# MainBoard_ver2_2.net
KiCad netlist of a schematic drawn in EAGLE
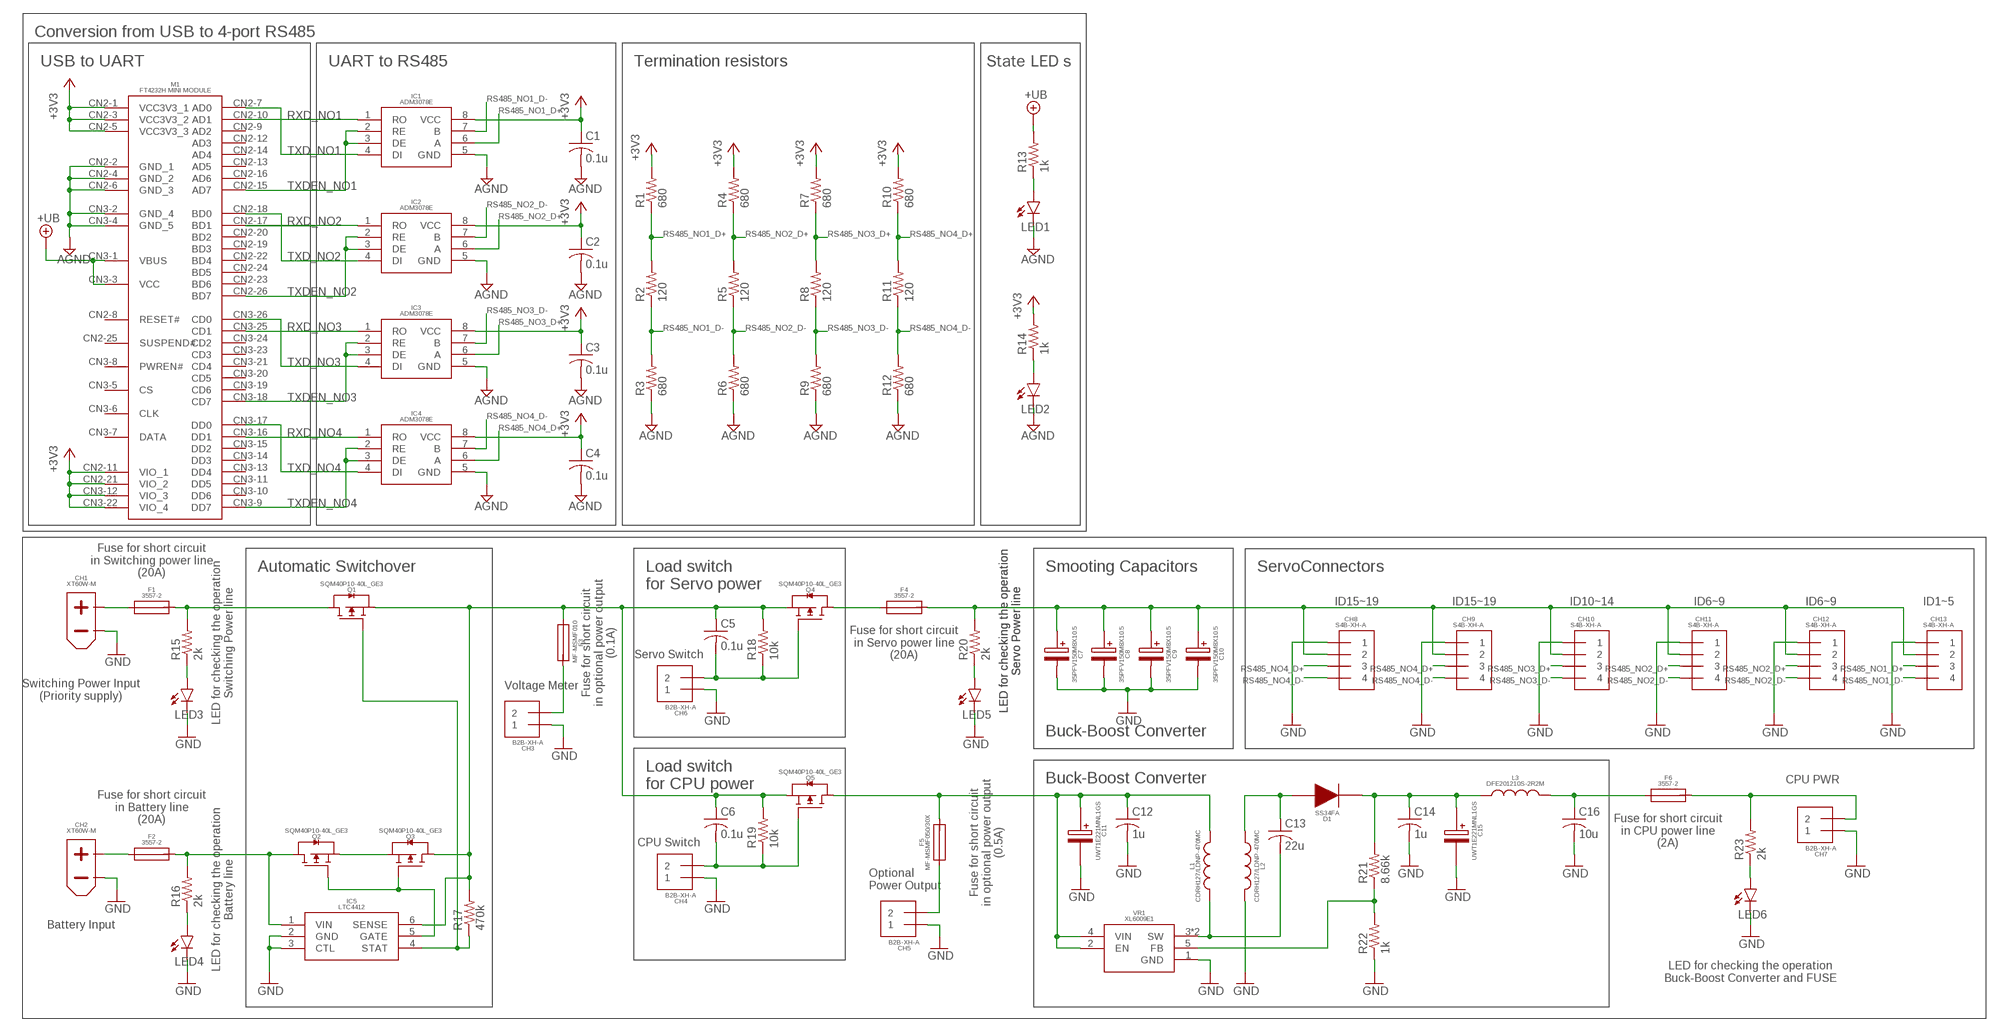
[diagram p0: schematic, sheet 1]

(export (version "E")
  (design (tool "Eeschema 10.0.6"))
  (components
    (comp (ref "C1")
      (value "0.1u")
      (footprint "eagle-import:C0603")
      (libsource (lib "eagle-import") (part "C-USC0603"))
    )
    (comp (ref "C2")
      (value "0.1u")
      (footprint "eagle-import:C0603")
      (libsource (lib "eagle-import") (part "C-USC0603"))
    )
    (comp (ref "C3")
      (value "0.1u")
      (footprint "eagle-import:C0603")
      (libsource (lib "eagle-import") (part "C-USC0603"))
    )
    (comp (ref "C4")
      (value "0.1u")
      (footprint "eagle-import:C0603")
      (libsource (lib "eagle-import") (part "C-USC0603"))
    )
    (comp (ref "C5")
      (value "0.1u")
      (footprint "eagle-import:C0603")
      (libsource (lib "eagle-import") (part "C-USC0603"))
    )
    (comp (ref "C6")
      (value "0.1u")
      (footprint "eagle-import:C0603")
      (libsource (lib "eagle-import") (part "C-USC0603"))
    )
    (comp (ref "C7")
      (value "35PFV150M8X10.5")
      (footprint "eagle-import:35PFV150M8X10.5")
      (libsource (lib "eagle-import") (part "35PFV150M8X10.5"))
    )
    (comp (ref "C8")
      (value "35PFV150M8X10.5")
      (footprint "eagle-import:35PFV150M8X10.5")
      (libsource (lib "eagle-import") (part "35PFV150M8X10.5"))
    )
    (comp (ref "C9")
      (value "35PFV150M8X10.5")
      (footprint "eagle-import:35PFV150M8X10.5")
      (libsource (lib "eagle-import") (part "35PFV150M8X10.5"))
    )
    (comp (ref "C10")
      (value "35PFV150M8X10.5")
      (footprint "eagle-import:35PFV150M8X10.5")
      (libsource (lib "eagle-import") (part "35PFV150M8X10.5"))
    )
    (comp (ref "C11")
      (value "UWT1E221MNL1GS")
      (footprint "eagle-import:UWT1E221MNL1GS")
      (libsource (lib "eagle-import") (part "UWT1E221MNL1GS"))
    )
    (comp (ref "C12")
      (value "1u")
      (footprint "eagle-import:C0603")
      (libsource (lib "eagle-import") (part "C-USC0603"))
    )
    (comp (ref "C13")
      (value "22u")
      (footprint "eagle-import:C2012")
      (libsource (lib "eagle-import") (part "C-USC2012"))
    )
    (comp (ref "C14")
      (value "1u")
      (footprint "eagle-import:C0603")
      (libsource (lib "eagle-import") (part "C-USC0603"))
    )
    (comp (ref "C15")
      (value "UWT1E221MNL1GS")
      (footprint "eagle-import:UWT1E221MNL1GS")
      (libsource (lib "eagle-import") (part "UWT1E221MNL1GS"))
    )
    (comp (ref "C16")
      (value "10u")
      (footprint "eagle-import:C0603")
      (libsource (lib "eagle-import") (part "C-USC0603"))
    )
    (comp (ref "CH1")
      (value "XT60PW-M")
      (footprint "eagle-import:XT60PW-M")
      (libsource (lib "eagle-import") (part "XT60PW-M"))
    )
    (comp (ref "CH2")
      (value "XT60PW-M")
      (footprint "eagle-import:XT60PW-M")
      (libsource (lib "eagle-import") (part "XT60PW-M"))
    )
    (comp (ref "CH3")
      (value "B2B-XH-A")
      (footprint "eagle-import:B2B-XH-A")
      (libsource (lib "eagle-import") (part "B2B-XH-A"))
    )
    (comp (ref "CH4")
      (value "B2B-XH-A")
      (footprint "eagle-import:B2B-XH-A")
      (libsource (lib "eagle-import") (part "B2B-XH-A"))
    )
    (comp (ref "CH5")
      (value "B2B-XH-A")
      (footprint "eagle-import:B2B-XH-A")
      (libsource (lib "eagle-import") (part "B2B-XH-A"))
    )
    (comp (ref "CH6")
      (value "B2B-XH-A")
      (footprint "eagle-import:B2B-XH-A")
      (libsource (lib "eagle-import") (part "B2B-XH-A"))
    )
    (comp (ref "CH7")
      (value "B2B-XH-A")
      (footprint "eagle-import:B2B-XH-A")
      (libsource (lib "eagle-import") (part "B2B-XH-A"))
    )
    (comp (ref "CH8")
      (value "S4B-XH-A")
      (footprint "eagle-import:S4B-XH-A")
      (libsource (lib "eagle-import") (part "S4B-XH-A"))
    )
    (comp (ref "CH9")
      (value "S4B-XH-A")
      (footprint "eagle-import:S4B-XH-A")
      (libsource (lib "eagle-import") (part "S4B-XH-A"))
    )
    (comp (ref "CH10")
      (value "S4B-XH-A")
      (footprint "eagle-import:S4B-XH-A")
      (libsource (lib "eagle-import") (part "S4B-XH-A"))
    )
    (comp (ref "CH11")
      (value "S4B-XH-A")
      (footprint "eagle-import:S4B-XH-A")
      (libsource (lib "eagle-import") (part "S4B-XH-A"))
    )
    (comp (ref "CH12")
      (value "S4B-XH-A")
      (footprint "eagle-import:S4B-XH-A")
      (libsource (lib "eagle-import") (part "S4B-XH-A"))
    )
    (comp (ref "CH13")
      (value "S4B-XH-A")
      (footprint "eagle-import:S4B-XH-A")
      (libsource (lib "eagle-import") (part "S4B-XH-A"))
    )
    (comp (ref "D1")
      (value "SS34FA")
      (footprint "eagle-import:SS34FA")
      (libsource (lib "eagle-import") (part "SS34FA"))
    )
    (comp (ref "F1")
      (value "3557-2")
      (footprint "eagle-import:3557-2")
      (libsource (lib "eagle-import") (part "3557-2"))
    )
    (comp (ref "F2")
      (value "3557-2")
      (footprint "eagle-import:3557-2")
      (libsource (lib "eagle-import") (part "3557-2"))
    )
    (comp (ref "F3")
      (value "MF-MSMF010")
      (footprint "eagle-import:MF-MSMF010")
      (libsource (lib "eagle-import") (part "MF-MSMF010"))
    )
    (comp (ref "F4")
      (value "3557-2")
      (footprint "eagle-import:3557-2")
      (libsource (lib "eagle-import") (part "3557-2"))
    )
    (comp (ref "F5")
      (value "MF-MSMF050/30X")
      (footprint "eagle-import:MF-MSMF050")
      (libsource (lib "eagle-import") (part "MF-MSMF050/30X"))
    )
    (comp (ref "F6")
      (value "3557-2")
      (footprint "eagle-import:3557-2")
      (libsource (lib "eagle-import") (part "3557-2"))
    )
    (comp (ref "IC1")
      (value "ADM3078E")
      (footprint "eagle-import:ADM3078E")
      (libsource (lib "eagle-import") (part "ADM3078E"))
    )
    (comp (ref "IC2")
      (value "ADM3078E")
      (footprint "eagle-import:ADM3078E")
      (libsource (lib "eagle-import") (part "ADM3078E"))
    )
    (comp (ref "IC3")
      (value "ADM3078E")
      (footprint "eagle-import:ADM3078E")
      (libsource (lib "eagle-import") (part "ADM3078E"))
    )
    (comp (ref "IC4")
      (value "ADM3078E")
      (footprint "eagle-import:ADM3078E")
      (libsource (lib "eagle-import") (part "ADM3078E"))
    )
    (comp (ref "IC5")
      (value "LTC4412")
      (footprint "eagle-import:LTC4412")
      (libsource (lib "eagle-import") (part "LTC4412"))
    )
    (comp (ref "L1")
      (value "CDRH127/LDNP-470MC")
      (footprint "eagle-import:CDRH127_LDNP")
      (libsource (lib "eagle-import") (part "CDRH127/LDNP-470MC"))
    )
    (comp (ref "L2")
      (value "CDRH127/LDNP-470MC")
      (footprint "eagle-import:CDRH127_LDNP")
      (libsource (lib "eagle-import") (part "CDRH127/LDNP-470MC"))
    )
    (comp (ref "L3")
      (value "DFE201210S-2R2M")
      (footprint "eagle-import:DFE201210S")
      (libsource (lib "eagle-import") (part "DFE201210S-2R2M"))
    )
    (comp (ref "LED1")
      (value "LEDSML0603")
      (footprint "eagle-import:SML0603")
      (libsource (lib "eagle-import") (part "LEDSML0603"))
    )
    (comp (ref "LED2")
      (value "LEDSML0603")
      (footprint "eagle-import:SML0603")
      (libsource (lib "eagle-import") (part "LEDSML0603"))
    )
    (comp (ref "LED3")
      (value "LEDSML0603")
      (footprint "eagle-import:SML0603")
      (libsource (lib "eagle-import") (part "LEDSML0603"))
    )
    (comp (ref "LED4")
      (value "LEDSML0603")
      (footprint "eagle-import:SML0603")
      (libsource (lib "eagle-import") (part "LEDSML0603"))
    )
    (comp (ref "LED5")
      (value "LEDSML0603")
      (footprint "eagle-import:SML0603")
      (libsource (lib "eagle-import") (part "LEDSML0603"))
    )
    (comp (ref "LED6")
      (value "LEDSML0603")
      (footprint "eagle-import:SML0603")
      (libsource (lib "eagle-import") (part "LEDSML0603"))
    )
    (comp (ref "M1")
      (value "FT4232H_MINI_MODULE")
      (footprint "eagle-import:FT4232H_MINI_MODULE")
      (libsource (lib "eagle-import") (part "FT4232H_MINI_MODULE"))
    )
    (comp (ref "Q1")
      (value "SQM40P10-40L_GE3")
      (footprint "eagle-import:TO-252-3")
      (libsource (lib "eagle-import") (part "SQM40P10-40L_GE3"))
    )
    (comp (ref "Q2")
      (value "SQM40P10-40L_GE3")
      (footprint "eagle-import:TO-252-3")
      (libsource (lib "eagle-import") (part "SQM40P10-40L_GE3"))
    )
    (comp (ref "Q3")
      (value "SQM40P10-40L_GE3")
      (footprint "eagle-import:TO-252-3")
      (libsource (lib "eagle-import") (part "SQM40P10-40L_GE3"))
    )
    (comp (ref "Q4")
      (value "SQM40P10-40L_GE3")
      (footprint "eagle-import:TO-252-3")
      (libsource (lib "eagle-import") (part "SQM40P10-40L_GE3"))
    )
    (comp (ref "Q5")
      (value "SQM40P10-40L_GE3")
      (footprint "eagle-import:TO-252-3")
      (libsource (lib "eagle-import") (part "SQM40P10-40L_GE3"))
    )
    (comp (ref "R1")
      (value "680")
      (footprint "eagle-import:R0603")
      (libsource (lib "eagle-import") (part "R-US_R0603"))
    )
    (comp (ref "R2")
      (value "120")
      (footprint "eagle-import:R0603")
      (libsource (lib "eagle-import") (part "R-US_R0603"))
    )
    (comp (ref "R3")
      (value "680")
      (footprint "eagle-import:R0603")
      (libsource (lib "eagle-import") (part "R-US_R0603"))
    )
    (comp (ref "R4")
      (value "680")
      (footprint "eagle-import:R0603")
      (libsource (lib "eagle-import") (part "R-US_R0603"))
    )
    (comp (ref "R5")
      (value "120")
      (footprint "eagle-import:R0603")
      (libsource (lib "eagle-import") (part "R-US_R0603"))
    )
    (comp (ref "R6")
      (value "680")
      (footprint "eagle-import:R0603")
      (libsource (lib "eagle-import") (part "R-US_R0603"))
    )
    (comp (ref "R7")
      (value "680")
      (footprint "eagle-import:R0603")
      (libsource (lib "eagle-import") (part "R-US_R0603"))
    )
    (comp (ref "R8")
      (value "120")
      (footprint "eagle-import:R0603")
      (libsource (lib "eagle-import") (part "R-US_R0603"))
    )
    (comp (ref "R9")
      (value "680")
      (footprint "eagle-import:R0603")
      (libsource (lib "eagle-import") (part "R-US_R0603"))
    )
    (comp (ref "R10")
      (value "680")
      (footprint "eagle-import:R0603")
      (libsource (lib "eagle-import") (part "R-US_R0603"))
    )
    (comp (ref "R11")
      (value "120")
      (footprint "eagle-import:R0603")
      (libsource (lib "eagle-import") (part "R-US_R0603"))
    )
    (comp (ref "R12")
      (value "680")
      (footprint "eagle-import:R0603")
      (libsource (lib "eagle-import") (part "R-US_R0603"))
    )
    (comp (ref "R13")
      (value "1k")
      (footprint "eagle-import:R0603")
      (libsource (lib "eagle-import") (part "R-US_R0603"))
    )
    (comp (ref "R14")
      (value "1k")
      (footprint "eagle-import:R0603")
      (libsource (lib "eagle-import") (part "R-US_R0603"))
    )
    (comp (ref "R15")
      (value "2k")
      (footprint "eagle-import:R0603")
      (libsource (lib "eagle-import") (part "R-US_R0603"))
    )
    (comp (ref "R16")
      (value "2k")
      (footprint "eagle-import:R0603")
      (libsource (lib "eagle-import") (part "R-US_R0603"))
    )
    (comp (ref "R17")
      (value "470k")
      (footprint "eagle-import:R0603")
      (libsource (lib "eagle-import") (part "R-US_R0603"))
    )
    (comp (ref "R18")
      (value "10k")
      (footprint "eagle-import:R0603")
      (libsource (lib "eagle-import") (part "R-US_R0603"))
    )
    (comp (ref "R19")
      (value "10k")
      (footprint "eagle-import:R0603")
      (libsource (lib "eagle-import") (part "R-US_R0603"))
    )
    (comp (ref "R20")
      (value "2k")
      (footprint "eagle-import:R0603")
      (libsource (lib "eagle-import") (part "R-US_R0603"))
    )
    (comp (ref "R21")
      (value "8.66k")
      (footprint "eagle-import:R0603")
      (libsource (lib "eagle-import") (part "R-US_R0603"))
    )
    (comp (ref "R22")
      (value "1k")
      (footprint "eagle-import:R0603")
      (libsource (lib "eagle-import") (part "R-US_R0603"))
    )
    (comp (ref "R23")
      (value "2k")
      (footprint "eagle-import:R0603")
      (libsource (lib "eagle-import") (part "R-US_R0603"))
    )
    (comp (ref "VR1")
      (value "XL6009E1")
      (footprint "eagle-import:TO263-5L")
      (libsource (lib "eagle-import") (part "XL6009E1"))
    )
  )
  (nets
    (net (code "1") (name "+3V3") (class "Default")
      (node (ref "C1") (pin "1") (pinfunction "1_1") (pintype "passive"))
      (node (ref "C2") (pin "1") (pinfunction "1_1") (pintype "passive"))
      (node (ref "C3") (pin "1") (pinfunction "1_1") (pintype "passive"))
      (node (ref "C4") (pin "1") (pinfunction "1_1") (pintype "passive"))
      (node (ref "IC1") (pin "8") (pinfunction "VCC_8") (pintype "bidirectional"))
      (node (ref "IC2") (pin "8") (pinfunction "VCC_8") (pintype "bidirectional"))
      (node (ref "IC3") (pin "8") (pinfunction "VCC_8") (pintype "bidirectional"))
      (node (ref "IC4") (pin "8") (pinfunction "VCC_8") (pintype "bidirectional"))
      (node (ref "M1") (pin "CN2-1") (pinfunction "VCC3V3_1_CN2-1") (pintype "bidirectional"))
      (node (ref "M1") (pin "CN2-11") (pinfunction "VIO_1_CN2-11") (pintype "bidirectional"))
      (node (ref "M1") (pin "CN2-21") (pinfunction "VIO_2_CN2-21") (pintype "bidirectional"))
      (node (ref "M1") (pin "CN2-3") (pinfunction "VCC3V3_2_CN2-3") (pintype "bidirectional"))
      (node (ref "M1") (pin "CN2-5") (pinfunction "VCC3V3_3_CN2-5") (pintype "bidirectional"))
      (node (ref "M1") (pin "CN3-12") (pinfunction "VIO_3_CN3-12") (pintype "bidirectional"))
      (node (ref "M1") (pin "CN3-22") (pinfunction "VIO_4_CN3-22") (pintype "bidirectional"))
      (node (ref "R1") (pin "2") (pinfunction "2_2") (pintype "passive"))
      (node (ref "R10") (pin "2") (pinfunction "2_2") (pintype "passive"))
      (node (ref "R14") (pin "2") (pinfunction "2_2") (pintype "passive"))
      (node (ref "R4") (pin "2") (pinfunction "2_2") (pintype "passive"))
      (node (ref "R7") (pin "2") (pinfunction "2_2") (pintype "passive"))
    )
    (net (code "2") (name "+UB") (class "Default")
      (node (ref "M1") (pin "CN3-1") (pinfunction "VBUS_CN3-1") (pintype "bidirectional"))
      (node (ref "M1") (pin "CN3-3") (pinfunction "VCC_CN3-3") (pintype "bidirectional"))
      (node (ref "R13") (pin "2") (pinfunction "2_2") (pintype "passive"))
    )
    (net (code "3") (name "/RS485_NO1_D+") (class "Default")
      (node (ref "CH13") (pin "3") (pinfunction "3_3") (pintype "bidirectional"))
      (node (ref "IC1") (pin "6") (pinfunction "A_6") (pintype "bidirectional"))
      (node (ref "R1") (pin "1") (pinfunction "1_1") (pintype "passive"))
      (node (ref "R2") (pin "2") (pinfunction "2_2") (pintype "passive"))
    )
    (net (code "4") (name "/RS485_NO1_D-") (class "Default")
      (node (ref "CH13") (pin "4") (pinfunction "4_4") (pintype "bidirectional"))
      (node (ref "IC1") (pin "7") (pinfunction "B_7") (pintype "bidirectional"))
      (node (ref "R2") (pin "1") (pinfunction "1_1") (pintype "passive"))
      (node (ref "R3") (pin "2") (pinfunction "2_2") (pintype "passive"))
    )
    (net (code "5") (name "/RS485_NO2_D+") (class "Default")
      (node (ref "CH11") (pin "3") (pinfunction "3_3") (pintype "bidirectional"))
      (node (ref "CH12") (pin "3") (pinfunction "3_3") (pintype "bidirectional"))
      (node (ref "IC2") (pin "6") (pinfunction "A_6") (pintype "bidirectional"))
      (node (ref "R4") (pin "1") (pinfunction "1_1") (pintype "passive"))
      (node (ref "R5") (pin "2") (pinfunction "2_2") (pintype "passive"))
    )
    (net (code "6") (name "/RS485_NO2_D-") (class "Default")
      (node (ref "CH11") (pin "4") (pinfunction "4_4") (pintype "bidirectional"))
      (node (ref "CH12") (pin "4") (pinfunction "4_4") (pintype "bidirectional"))
      (node (ref "IC2") (pin "7") (pinfunction "B_7") (pintype "bidirectional"))
      (node (ref "R5") (pin "1") (pinfunction "1_1") (pintype "passive"))
      (node (ref "R6") (pin "2") (pinfunction "2_2") (pintype "passive"))
    )
    (net (code "7") (name "/RS485_NO3_D+") (class "Default")
      (node (ref "CH10") (pin "3") (pinfunction "3_3") (pintype "bidirectional"))
      (node (ref "IC3") (pin "6") (pinfunction "A_6") (pintype "bidirectional"))
      (node (ref "R7") (pin "1") (pinfunction "1_1") (pintype "passive"))
      (node (ref "R8") (pin "2") (pinfunction "2_2") (pintype "passive"))
    )
    (net (code "8") (name "/RS485_NO3_D-") (class "Default")
      (node (ref "CH10") (pin "4") (pinfunction "4_4") (pintype "bidirectional"))
      (node (ref "IC3") (pin "7") (pinfunction "B_7") (pintype "bidirectional"))
      (node (ref "R8") (pin "1") (pinfunction "1_1") (pintype "passive"))
      (node (ref "R9") (pin "2") (pinfunction "2_2") (pintype "passive"))
    )
    (net (code "9") (name "/RS485_NO4_D+") (class "Default")
      (node (ref "CH8") (pin "3") (pinfunction "3_3") (pintype "bidirectional"))
      (node (ref "CH9") (pin "3") (pinfunction "3_3") (pintype "bidirectional"))
      (node (ref "IC4") (pin "6") (pinfunction "A_6") (pintype "bidirectional"))
      (node (ref "R10") (pin "1") (pinfunction "1_1") (pintype "passive"))
      (node (ref "R11") (pin "2") (pinfunction "2_2") (pintype "passive"))
    )
    (net (code "10") (name "/RS485_NO4_D-") (class "Default")
      (node (ref "CH8") (pin "4") (pinfunction "4_4") (pintype "bidirectional"))
      (node (ref "CH9") (pin "4") (pinfunction "4_4") (pintype "bidirectional"))
      (node (ref "IC4") (pin "7") (pinfunction "B_7") (pintype "bidirectional"))
      (node (ref "R11") (pin "1") (pinfunction "1_1") (pintype "passive"))
      (node (ref "R12") (pin "2") (pinfunction "2_2") (pintype "passive"))
    )
    (net (code "11") (name "/RXD_NO1") (class "Default")
      (node (ref "IC1") (pin "1") (pinfunction "RO_1") (pintype "bidirectional"))
      (node (ref "M1") (pin "CN2-10") (pinfunction "AD1_CN2-10") (pintype "bidirectional"))
    )
    (net (code "12") (name "/RXD_NO2") (class "Default")
      (node (ref "IC2") (pin "1") (pinfunction "RO_1") (pintype "bidirectional"))
      (node (ref "M1") (pin "CN2-17") (pinfunction "BD1_CN2-17") (pintype "bidirectional"))
    )
    (net (code "13") (name "/RXD_NO3") (class "Default")
      (node (ref "IC3") (pin "1") (pinfunction "RO_1") (pintype "bidirectional"))
      (node (ref "M1") (pin "CN3-25") (pinfunction "CD1_CN3-25") (pintype "bidirectional"))
    )
    (net (code "14") (name "/RXD_NO4") (class "Default")
      (node (ref "IC4") (pin "1") (pinfunction "RO_1") (pintype "bidirectional"))
      (node (ref "M1") (pin "CN3-16") (pinfunction "DD1_CN3-16") (pintype "bidirectional"))
    )
    (net (code "15") (name "/TXDEN_NO1") (class "Default")
      (node (ref "IC1") (pin "2") (pinfunction "RE_2") (pintype "bidirectional"))
      (node (ref "IC1") (pin "3") (pinfunction "DE_3") (pintype "bidirectional"))
      (node (ref "M1") (pin "CN2-15") (pinfunction "AD7_CN2-15") (pintype "bidirectional"))
    )
    (net (code "16") (name "/TXDEN_NO2") (class "Default")
      (node (ref "IC2") (pin "2") (pinfunction "RE_2") (pintype "bidirectional"))
      (node (ref "IC2") (pin "3") (pinfunction "DE_3") (pintype "bidirectional"))
      (node (ref "M1") (pin "CN2-26") (pinfunction "BD7_CN2-26") (pintype "bidirectional"))
    )
    (net (code "17") (name "/TXDEN_NO3") (class "Default")
      (node (ref "IC3") (pin "2") (pinfunction "RE_2") (pintype "bidirectional"))
      (node (ref "IC3") (pin "3") (pinfunction "DE_3") (pintype "bidirectional"))
      (node (ref "M1") (pin "CN3-18") (pinfunction "CD7_CN3-18") (pintype "bidirectional"))
    )
    (net (code "18") (name "/TXDEN_NO4") (class "Default")
      (node (ref "IC4") (pin "2") (pinfunction "RE_2") (pintype "bidirectional"))
      (node (ref "IC4") (pin "3") (pinfunction "DE_3") (pintype "bidirectional"))
      (node (ref "M1") (pin "CN3-9") (pinfunction "DD7_CN3-9") (pintype "bidirectional"))
    )
    (net (code "19") (name "/TXD_NO1") (class "Default")
      (node (ref "IC1") (pin "4") (pinfunction "DI_4") (pintype "bidirectional"))
      (node (ref "M1") (pin "CN2-7") (pinfunction "AD0_CN2-7") (pintype "bidirectional"))
    )
    (net (code "20") (name "/TXD_NO2") (class "Default")
      (node (ref "IC2") (pin "4") (pinfunction "DI_4") (pintype "bidirectional"))
      (node (ref "M1") (pin "CN2-18") (pinfunction "BD0_CN2-18") (pintype "bidirectional"))
    )
    (net (code "21") (name "/TXD_NO3") (class "Default")
      (node (ref "IC3") (pin "4") (pinfunction "DI_4") (pintype "bidirectional"))
      (node (ref "M1") (pin "CN3-26") (pinfunction "CD0_CN3-26") (pintype "bidirectional"))
    )
    (net (code "22") (name "/TXD_NO4") (class "Default")
      (node (ref "IC4") (pin "4") (pinfunction "DI_4") (pintype "bidirectional"))
      (node (ref "M1") (pin "CN3-17") (pinfunction "DD0_CN3-17") (pintype "bidirectional"))
    )
    (net (code "23") (name "AGND") (class "Default")
      (node (ref "C1") (pin "2") (pinfunction "2_2") (pintype "passive"))
      (node (ref "C2") (pin "2") (pinfunction "2_2") (pintype "passive"))
      (node (ref "C3") (pin "2") (pinfunction "2_2") (pintype "passive"))
      (node (ref "C4") (pin "2") (pinfunction "2_2") (pintype "passive"))
      (node (ref "IC1") (pin "5") (pinfunction "GND_5") (pintype "bidirectional"))
      (node (ref "IC2") (pin "5") (pinfunction "GND_5") (pintype "bidirectional"))
      (node (ref "IC3") (pin "5") (pinfunction "GND_5") (pintype "bidirectional"))
      (node (ref "IC4") (pin "5") (pinfunction "GND_5") (pintype "bidirectional"))
      (node (ref "LED1") (pin "C") (pinfunction "C_C") (pintype "passive"))
      (node (ref "LED2") (pin "C") (pinfunction "C_C") (pintype "passive"))
      (node (ref "M1") (pin "CN2-2") (pinfunction "GND_1_CN2-2") (pintype "bidirectional"))
      (node (ref "M1") (pin "CN2-4") (pinfunction "GND_2_CN2-4") (pintype "bidirectional"))
      (node (ref "M1") (pin "CN2-6") (pinfunction "GND_3_CN2-6") (pintype "bidirectional"))
      (node (ref "M1") (pin "CN3-2") (pinfunction "GND_4_CN3-2") (pintype "bidirectional"))
      (node (ref "M1") (pin "CN3-4") (pinfunction "GND_5_CN3-4") (pintype "bidirectional"))
      (node (ref "R12") (pin "1") (pinfunction "1_1") (pintype "passive"))
      (node (ref "R3") (pin "1") (pinfunction "1_1") (pintype "passive"))
      (node (ref "R6") (pin "1") (pinfunction "1_1") (pintype "passive"))
      (node (ref "R9") (pin "1") (pinfunction "1_1") (pintype "passive"))
    )
    (net (code "24") (name "GND") (class "Default")
      (node (ref "C10") (pin "-") (pinfunction "-_-") (pintype "bidirectional"))
      (node (ref "C11") (pin "-") (pinfunction "-_-") (pintype "bidirectional"))
      (node (ref "C12") (pin "2") (pinfunction "2_2") (pintype "passive"))
      (node (ref "C14") (pin "2") (pinfunction "2_2") (pintype "passive"))
      (node (ref "C15") (pin "-") (pinfunction "-_-") (pintype "bidirectional"))
      (node (ref "C16") (pin "2") (pinfunction "2_2") (pintype "passive"))
      (node (ref "C7") (pin "-") (pinfunction "-_-") (pintype "bidirectional"))
      (node (ref "C8") (pin "-") (pinfunction "-_-") (pintype "bidirectional"))
      (node (ref "C9") (pin "-") (pinfunction "-_-") (pintype "bidirectional"))
      (node (ref "CH1") (pin "-") (pinfunction "-_-") (pintype "power_in"))
      (node (ref "CH10") (pin "1") (pinfunction "1_1") (pintype "bidirectional"))
      (node (ref "CH11") (pin "1") (pinfunction "1_1") (pintype "bidirectional"))
      (node (ref "CH12") (pin "1") (pinfunction "1_1") (pintype "bidirectional"))
      (node (ref "CH13") (pin "1") (pinfunction "1_1") (pintype "bidirectional"))
      (node (ref "CH2") (pin "-") (pinfunction "-_-") (pintype "power_in"))
      (node (ref "CH3") (pin "1") (pinfunction "1_1") (pintype "bidirectional"))
      (node (ref "CH4") (pin "1") (pinfunction "1_1") (pintype "bidirectional"))
      (node (ref "CH5") (pin "1") (pinfunction "1_1") (pintype "bidirectional"))
      (node (ref "CH6") (pin "1") (pinfunction "1_1") (pintype "bidirectional"))
      (node (ref "CH7") (pin "1") (pinfunction "1_1") (pintype "bidirectional"))
      (node (ref "CH8") (pin "1") (pinfunction "1_1") (pintype "bidirectional"))
      (node (ref "CH9") (pin "1") (pinfunction "1_1") (pintype "bidirectional"))
      (node (ref "IC5") (pin "2") (pinfunction "GND_2") (pintype "bidirectional"))
      (node (ref "IC5") (pin "3") (pinfunction "CTL_3") (pintype "bidirectional"))
      (node (ref "L2") (pin "2") (pinfunction "2_2") (pintype "bidirectional"))
      (node (ref "LED3") (pin "C") (pinfunction "C_C") (pintype "passive"))
      (node (ref "LED4") (pin "C") (pinfunction "C_C") (pintype "passive"))
      (node (ref "LED5") (pin "C") (pinfunction "C_C") (pintype "passive"))
      (node (ref "LED6") (pin "C") (pinfunction "C_C") (pintype "passive"))
      (node (ref "R22") (pin "1") (pinfunction "1_1") (pintype "passive"))
      (node (ref "VR1") (pin "1") (pinfunction "GND_1") (pintype "power_in"))
    )
    (net (code "25") (name "Net-(C10-Pad+)") (class "Default")
      (node (ref "C10") (pin "+") (pinfunction "+_+") (pintype "bidirectional"))
      (node (ref "C7") (pin "+") (pinfunction "+_+") (pintype "bidirectional"))
      (node (ref "C8") (pin "+") (pinfunction "+_+") (pintype "bidirectional"))
      (node (ref "C9") (pin "+") (pinfunction "+_+") (pintype "bidirectional"))
      (node (ref "CH10") (pin "2") (pinfunction "2_2") (pintype "bidirectional"))
      (node (ref "CH11") (pin "2") (pinfunction "2_2") (pintype "bidirectional"))
      (node (ref "CH12") (pin "2") (pinfunction "2_2") (pintype "bidirectional"))
      (node (ref "CH13") (pin "2") (pinfunction "2_2") (pintype "bidirectional"))
      (node (ref "CH8") (pin "2") (pinfunction "2_2") (pintype "bidirectional"))
      (node (ref "CH9") (pin "2") (pinfunction "2_2") (pintype "bidirectional"))
      (node (ref "F4") (pin "3") (pinfunction "2_3") (pintype "bidirectional"))
      (node (ref "F4") (pin "4") (pinfunction "2_4") (pintype "bidirectional"))
      (node (ref "R20") (pin "2") (pinfunction "2_2") (pintype "passive"))
    )
    (net (code "26") (name "Net-(C13-Pad1)") (class "Default")
      (node (ref "C13") (pin "1") (pinfunction "1_1") (pintype "passive"))
      (node (ref "D1") (pin "2") (pinfunction "2_2") (pintype "bidirectional"))
      (node (ref "L2") (pin "1") (pinfunction "1_1") (pintype "bidirectional"))
    )
    (net (code "27") (name "Net-(C13-Pad2)") (class "Default")
      (node (ref "C13") (pin "2") (pinfunction "2_2") (pintype "passive"))
      (node (ref "L1") (pin "1") (pinfunction "1_1") (pintype "bidirectional"))
      (node (ref "VR1") (pin "3") (pinfunction "SW_3") (pintype "output"))
      (node (ref "VR1") (pin "6") (pinfunction "SW_6") (pintype "output"))
    )
    (net (code "28") (name "Net-(CH1-Pad+)") (class "Default")
      (node (ref "CH1") (pin "+") (pinfunction "+_+") (pintype "power_in"))
      (node (ref "F1") (pin "1") (pinfunction "1_1") (pintype "bidirectional"))
      (node (ref "F1") (pin "2") (pinfunction "1_2") (pintype "bidirectional"))
    )
    (net (code "29") (name "Net-(CH2-Pad+)") (class "Default")
      (node (ref "CH2") (pin "+") (pinfunction "+_+") (pintype "power_in"))
      (node (ref "F2") (pin "1") (pinfunction "1_1") (pintype "bidirectional"))
      (node (ref "F2") (pin "2") (pinfunction "1_2") (pintype "bidirectional"))
    )
    (net (code "30") (name "Net-(CH3-Pad2)") (class "Default")
      (node (ref "CH3") (pin "2") (pinfunction "2_2") (pintype "bidirectional"))
      (node (ref "F3") (pin "2") (pinfunction "2_2") (pintype "bidirectional"))
    )
    (net (code "31") (name "Net-(CH5-Pad2)") (class "Default")
      (node (ref "CH5") (pin "2") (pinfunction "2_2") (pintype "bidirectional"))
      (node (ref "F5") (pin "1") (pinfunction "1_1") (pintype "bidirectional"))
    )
    (net (code "32") (name "Net-(CH7-Pad2)") (class "Default")
      (node (ref "CH7") (pin "2") (pinfunction "2_2") (pintype "bidirectional"))
      (node (ref "F6") (pin "3") (pinfunction "2_3") (pintype "bidirectional"))
      (node (ref "F6") (pin "4") (pinfunction "2_4") (pintype "bidirectional"))
      (node (ref "R23") (pin "2") (pinfunction "2_2") (pintype "passive"))
    )
    (net (code "33") (name "Net-(IC5-GATE)") (class "Default")
      (node (ref "IC5") (pin "5") (pinfunction "GATE_5") (pintype "bidirectional"))
      (node (ref "Q2") (pin "1") (pinfunction "G_1") (pintype "bidirectional"))
      (node (ref "Q3") (pin "1") (pinfunction "G_1") (pintype "bidirectional"))
    )
    (net (code "34") (name "Net-(IC5-SENSE)") (class "Default")
      (node (ref "C5") (pin "1") (pinfunction "1_1") (pintype "passive"))
      (node (ref "C6") (pin "1") (pinfunction "1_1") (pintype "passive"))
      (node (ref "F3") (pin "1") (pinfunction "1_1") (pintype "bidirectional"))
      (node (ref "IC5") (pin "6") (pinfunction "SENSE_6") (pintype "bidirectional"))
      (node (ref "Q1") (pin "3") (pinfunction "S_3") (pintype "bidirectional"))
      (node (ref "Q3") (pin "4") (pinfunction "D_4") (pintype "bidirectional"))
      (node (ref "Q4") (pin "3") (pinfunction "S_3") (pintype "bidirectional"))
      (node (ref "Q5") (pin "3") (pinfunction "S_3") (pintype "bidirectional"))
      (node (ref "R17") (pin "2") (pinfunction "2_2") (pintype "passive"))
      (node (ref "R18") (pin "2") (pinfunction "2_2") (pintype "passive"))
      (node (ref "R19") (pin "2") (pinfunction "2_2") (pintype "passive"))
    )
    (net (code "35") (name "Net-(IC5-STAT)") (class "Default")
      (node (ref "IC5") (pin "4") (pinfunction "STAT_4") (pintype "bidirectional"))
      (node (ref "Q1") (pin "1") (pinfunction "G_1") (pintype "bidirectional"))
      (node (ref "R17") (pin "1") (pinfunction "1_1") (pintype "passive"))
    )
    (net (code "36") (name "Net-(IC5-VIN)") (class "Default")
      (node (ref "F2") (pin "3") (pinfunction "2_3") (pintype "bidirectional"))
      (node (ref "F2") (pin "4") (pinfunction "2_4") (pintype "bidirectional"))
      (node (ref "IC5") (pin "1") (pinfunction "VIN_1") (pintype "bidirectional"))
      (node (ref "Q2") (pin "4") (pinfunction "D_4") (pintype "bidirectional"))
      (node (ref "R16") (pin "2") (pinfunction "2_2") (pintype "passive"))
    )
    (net (code "37") (name "Net-(L3-P$1)") (class "Default")
      (node (ref "C14") (pin "1") (pinfunction "1_1") (pintype "passive"))
      (node (ref "C15") (pin "+") (pinfunction "+_+") (pintype "bidirectional"))
      (node (ref "D1") (pin "1") (pinfunction "1_1") (pintype "bidirectional"))
      (node (ref "L3") (pin "1") (pinfunction "P$1_1") (pintype "bidirectional"))
      (node (ref "R21") (pin "2") (pinfunction "2_2") (pintype "passive"))
    )
    (net (code "38") (name "Net-(L3-P$2)") (class "Default")
      (node (ref "C16") (pin "1") (pinfunction "1_1") (pintype "passive"))
      (node (ref "F6") (pin "1") (pinfunction "1_1") (pintype "bidirectional"))
      (node (ref "F6") (pin "2") (pinfunction "1_2") (pintype "bidirectional"))
      (node (ref "L3") (pin "2") (pinfunction "P$2_2") (pintype "bidirectional"))
    )
    (net (code "39") (name "Net-(LED1-PadA)") (class "Default")
      (node (ref "LED1") (pin "A") (pinfunction "A_A") (pintype "passive"))
      (node (ref "R13") (pin "1") (pinfunction "1_1") (pintype "passive"))
    )
    (net (code "40") (name "Net-(LED2-PadA)") (class "Default")
      (node (ref "LED2") (pin "A") (pinfunction "A_A") (pintype "passive"))
      (node (ref "R14") (pin "1") (pinfunction "1_1") (pintype "passive"))
    )
    (net (code "41") (name "Net-(LED3-PadA)") (class "Default")
      (node (ref "LED3") (pin "A") (pinfunction "A_A") (pintype "passive"))
      (node (ref "R15") (pin "1") (pinfunction "1_1") (pintype "passive"))
    )
    (net (code "42") (name "Net-(LED4-PadA)") (class "Default")
      (node (ref "LED4") (pin "A") (pinfunction "A_A") (pintype "passive"))
      (node (ref "R16") (pin "1") (pinfunction "1_1") (pintype "passive"))
    )
    (net (code "43") (name "Net-(LED5-PadA)") (class "Default")
      (node (ref "LED5") (pin "A") (pinfunction "A_A") (pintype "passive"))
      (node (ref "R20") (pin "1") (pinfunction "1_1") (pintype "passive"))
    )
    (net (code "44") (name "Net-(LED6-PadA)") (class "Default")
      (node (ref "LED6") (pin "A") (pinfunction "A_A") (pintype "passive"))
      (node (ref "R23") (pin "1") (pinfunction "1_1") (pintype "passive"))
    )
    (net (code "45") (name "Net-(Q1-D)") (class "Default")
      (node (ref "F1") (pin "3") (pinfunction "2_3") (pintype "bidirectional"))
      (node (ref "F1") (pin "4") (pinfunction "2_4") (pintype "bidirectional"))
      (node (ref "Q1") (pin "4") (pinfunction "D_4") (pintype "bidirectional"))
      (node (ref "R15") (pin "2") (pinfunction "2_2") (pintype "passive"))
    )
    (net (code "46") (name "Net-(Q2-S)") (class "Default")
      (node (ref "Q2") (pin "3") (pinfunction "S_3") (pintype "bidirectional"))
      (node (ref "Q3") (pin "3") (pinfunction "S_3") (pintype "bidirectional"))
    )
    (net (code "47") (name "Net-(Q4-D)") (class "Default")
      (node (ref "F4") (pin "1") (pinfunction "1_1") (pintype "bidirectional"))
      (node (ref "F4") (pin "2") (pinfunction "1_2") (pintype "bidirectional"))
      (node (ref "Q4") (pin "4") (pinfunction "D_4") (pintype "bidirectional"))
    )
    (net (code "48") (name "Net-(Q4-G)") (class "Default")
      (node (ref "C5") (pin "2") (pinfunction "2_2") (pintype "passive"))
      (node (ref "CH6") (pin "2") (pinfunction "2_2") (pintype "bidirectional"))
      (node (ref "Q4") (pin "1") (pinfunction "G_1") (pintype "bidirectional"))
      (node (ref "R18") (pin "1") (pinfunction "1_1") (pintype "passive"))
    )
    (net (code "49") (name "Net-(Q5-D)") (class "Default")
      (node (ref "C11") (pin "+") (pinfunction "+_+") (pintype "bidirectional"))
      (node (ref "C12") (pin "1") (pinfunction "1_1") (pintype "passive"))
      (node (ref "F5") (pin "2") (pinfunction "2_2") (pintype "bidirectional"))
      (node (ref "L1") (pin "2") (pinfunction "2_2") (pintype "bidirectional"))
      (node (ref "Q5") (pin "4") (pinfunction "D_4") (pintype "bidirectional"))
      (node (ref "VR1") (pin "2") (pinfunction "EN_2") (pintype "input"))
      (node (ref "VR1") (pin "4") (pinfunction "VIN_4") (pintype "input"))
    )
    (net (code "50") (name "Net-(Q5-G)") (class "Default")
      (node (ref "C6") (pin "2") (pinfunction "2_2") (pintype "passive"))
      (node (ref "CH4") (pin "2") (pinfunction "2_2") (pintype "bidirectional"))
      (node (ref "Q5") (pin "1") (pinfunction "G_1") (pintype "bidirectional"))
      (node (ref "R19") (pin "1") (pinfunction "1_1") (pintype "passive"))
    )
    (net (code "51") (name "Net-(VR1-FB)") (class "Default")
      (node (ref "R21") (pin "1") (pinfunction "1_1") (pintype "passive"))
      (node (ref "R22") (pin "2") (pinfunction "2_2") (pintype "passive"))
      (node (ref "VR1") (pin "5") (pinfunction "FB_5") (pintype "input"))
    )
    (net (code "52") (name "unconnected-(M1-AD2-PadCN2-9)") (class "Default")
      (node (ref "M1") (pin "CN2-9") (pinfunction "AD2_CN2-9") (pintype "bidirectional"))
    )
    (net (code "53") (name "unconnected-(M1-AD3-PadCN2-12)") (class "Default")
      (node (ref "M1") (pin "CN2-12") (pinfunction "AD3_CN2-12") (pintype "bidirectional"))
    )
    (net (code "54") (name "unconnected-(M1-AD4-PadCN2-14)") (class "Default")
      (node (ref "M1") (pin "CN2-14") (pinfunction "AD4_CN2-14") (pintype "bidirectional"))
    )
    (net (code "55") (name "unconnected-(M1-AD5-PadCN2-13)") (class "Default")
      (node (ref "M1") (pin "CN2-13") (pinfunction "AD5_CN2-13") (pintype "bidirectional"))
    )
    (net (code "56") (name "unconnected-(M1-AD6-PadCN2-16)") (class "Default")
      (node (ref "M1") (pin "CN2-16") (pinfunction "AD6_CN2-16") (pintype "bidirectional"))
    )
    (net (code "57") (name "unconnected-(M1-BD2-PadCN2-20)") (class "Default")
      (node (ref "M1") (pin "CN2-20") (pinfunction "BD2_CN2-20") (pintype "bidirectional"))
    )
    (net (code "58") (name "unconnected-(M1-BD3-PadCN2-19)") (class "Default")
      (node (ref "M1") (pin "CN2-19") (pinfunction "BD3_CN2-19") (pintype "bidirectional"))
    )
    (net (code "59") (name "unconnected-(M1-BD4-PadCN2-22)") (class "Default")
      (node (ref "M1") (pin "CN2-22") (pinfunction "BD4_CN2-22") (pintype "bidirectional"))
    )
    (net (code "60") (name "unconnected-(M1-BD5-PadCN2-24)") (class "Default")
      (node (ref "M1") (pin "CN2-24") (pinfunction "BD5_CN2-24") (pintype "bidirectional"))
    )
    (net (code "61") (name "unconnected-(M1-BD6-PadCN2-23)") (class "Default")
      (node (ref "M1") (pin "CN2-23") (pinfunction "BD6_CN2-23") (pintype "bidirectional"))
    )
    (net (code "62") (name "unconnected-(M1-CD2-PadCN3-24)") (class "Default")
      (node (ref "M1") (pin "CN3-24") (pinfunction "CD2_CN3-24") (pintype "bidirectional"))
    )
    (net (code "63") (name "unconnected-(M1-CD3-PadCN3-23)") (class "Default")
      (node (ref "M1") (pin "CN3-23") (pinfunction "CD3_CN3-23") (pintype "bidirectional"))
    )
    (net (code "64") (name "unconnected-(M1-CD4-PadCN3-21)") (class "Default")
      (node (ref "M1") (pin "CN3-21") (pinfunction "CD4_CN3-21") (pintype "bidirectional"))
    )
    (net (code "65") (name "unconnected-(M1-CD5-PadCN3-20)") (class "Default")
      (node (ref "M1") (pin "CN3-20") (pinfunction "CD5_CN3-20") (pintype "bidirectional"))
    )
    (net (code "66") (name "unconnected-(M1-CD6-PadCN3-19)") (class "Default")
      (node (ref "M1") (pin "CN3-19") (pinfunction "CD6_CN3-19") (pintype "bidirectional"))
    )
    (net (code "67") (name "unconnected-(M1-CLK-PadCN3-6)") (class "Default")
      (node (ref "M1") (pin "CN3-6") (pinfunction "CLK_CN3-6") (pintype "bidirectional"))
    )
    (net (code "68") (name "unconnected-(M1-CS-PadCN3-5)") (class "Default")
      (node (ref "M1") (pin "CN3-5") (pinfunction "CS_CN3-5") (pintype "bidirectional"))
    )
    (net (code "69") (name "unconnected-(M1-DATA-PadCN3-7)") (class "Default")
      (node (ref "M1") (pin "CN3-7") (pinfunction "DATA_CN3-7") (pintype "bidirectional"))
    )
    (net (code "70") (name "unconnected-(M1-DD2-PadCN3-15)") (class "Default")
      (node (ref "M1") (pin "CN3-15") (pinfunction "DD2_CN3-15") (pintype "bidirectional"))
    )
    (net (code "71") (name "unconnected-(M1-DD3-PadCN3-14)") (class "Default")
      (node (ref "M1") (pin "CN3-14") (pinfunction "DD3_CN3-14") (pintype "bidirectional"))
    )
    (net (code "72") (name "unconnected-(M1-DD4-PadCN3-13)") (class "Default")
      (node (ref "M1") (pin "CN3-13") (pinfunction "DD4_CN3-13") (pintype "bidirectional"))
    )
    (net (code "73") (name "unconnected-(M1-DD5-PadCN3-11)") (class "Default")
      (node (ref "M1") (pin "CN3-11") (pinfunction "DD5_CN3-11") (pintype "bidirectional"))
    )
    (net (code "74") (name "unconnected-(M1-DD6-PadCN3-10)") (class "Default")
      (node (ref "M1") (pin "CN3-10") (pinfunction "DD6_CN3-10") (pintype "bidirectional"))
    )
    (net (code "75") (name "unconnected-(M1-PWREN#-PadCN3-8)") (class "Default")
      (node (ref "M1") (pin "CN3-8") (pinfunction "PWREN#_CN3-8") (pintype "bidirectional"))
    )
    (net (code "76") (name "unconnected-(M1-RESET#-PadCN2-8)") (class "Default")
      (node (ref "M1") (pin "CN2-8") (pinfunction "RESET#_CN2-8") (pintype "bidirectional"))
    )
    (net (code "77") (name "unconnected-(M1-SUSPEND#-PadCN2-25)") (class "Default")
      (node (ref "M1") (pin "CN2-25") (pinfunction "SUSPEND#_CN2-25") (pintype "bidirectional"))
    )
  )
)
